# Lab7-8_CH4.net
KiCad netlist of a schematic drawn in Altium Designer
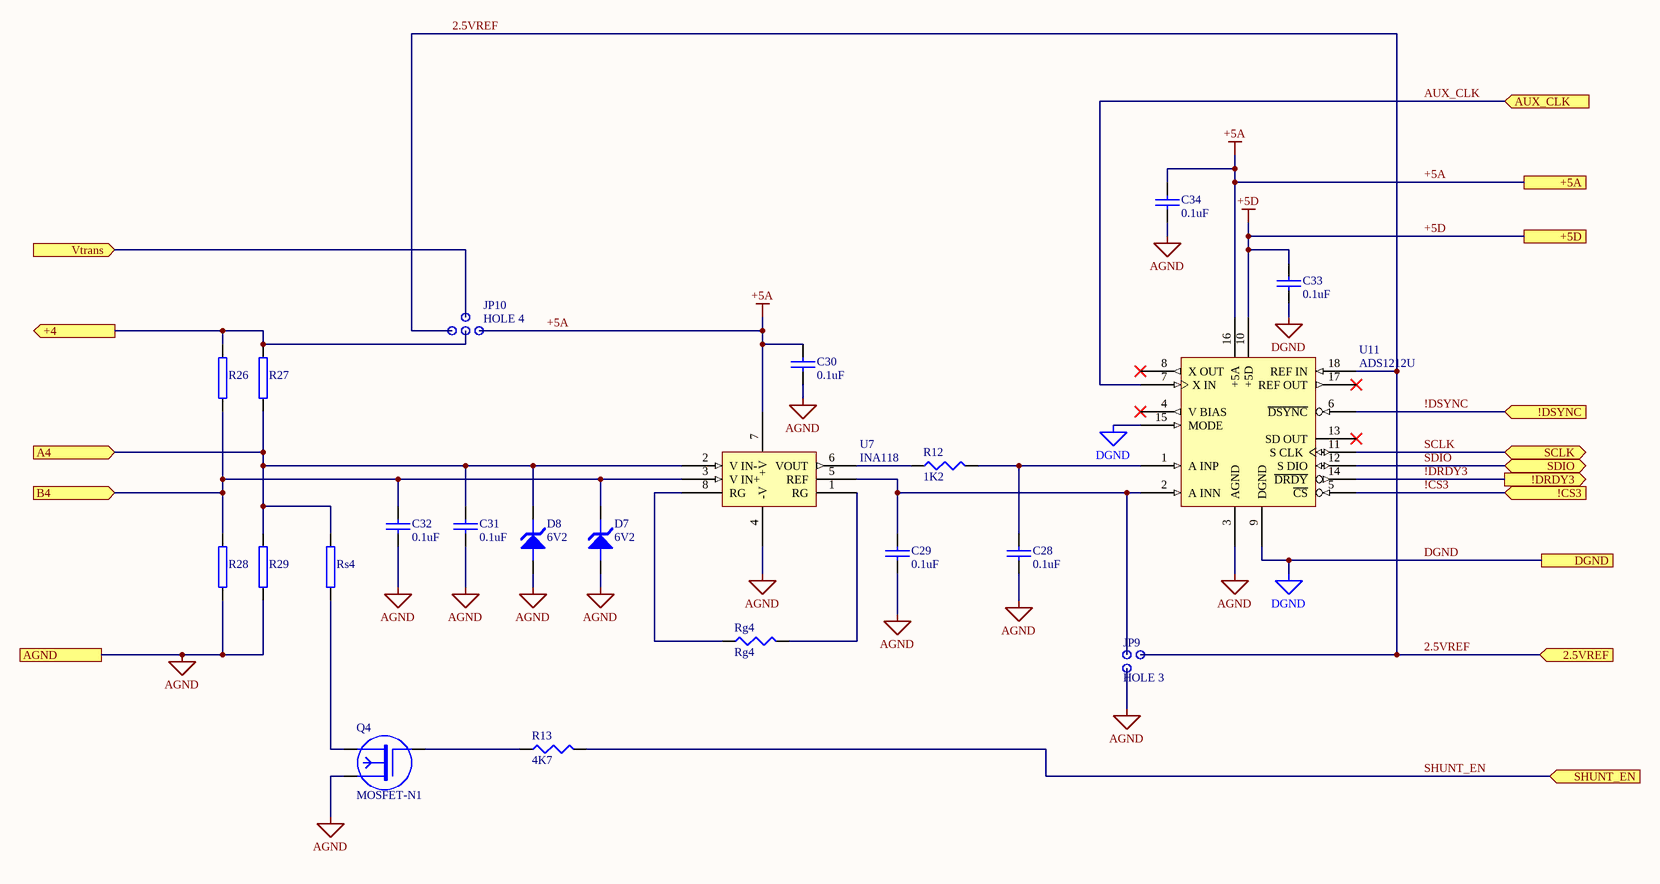
[diagram p0: Lab7-8_CH4.SchDoc]

(export (version "E")
  (design (tool "Eeschema 10.0.6"))
  (components
    (comp (ref "C28")
      (value "0.1uF")
      (footprint "0805")
      (libsource (lib "ECET231_ProjectThree_SCHLIB_Rev02") (part "CAP"))
    )
    (comp (ref "C29")
      (value "0.1uF")
      (footprint "0805")
      (libsource (lib "ECET231_ProjectThree_SCHLIB_Rev02") (part "CAP"))
    )
    (comp (ref "C30")
      (value "0.1uF")
      (footprint "0805")
      (libsource (lib "ECET231_ProjectThree_SCHLIB_Rev02") (part "CAP"))
    )
    (comp (ref "C31")
      (value "0.1uF")
      (footprint "0805")
      (libsource (lib "ECET231_ProjectThree_SCHLIB_Rev02") (part "CAP"))
    )
    (comp (ref "C32")
      (value "0.1uF")
      (footprint "0805")
      (libsource (lib "ECET231_ProjectThree_SCHLIB_Rev02") (part "CAP"))
    )
    (comp (ref "C33")
      (value "0.1uF")
      (footprint "0805")
      (libsource (lib "ECET231_ProjectThree_SCHLIB_Rev02") (part "CAP"))
    )
    (comp (ref "C34")
      (value "0.1uF")
      (footprint "0805")
      (libsource (lib "ECET231_ProjectThree_SCHLIB_Rev02") (part "CAP"))
    )
    (comp (ref "D7")
      (value "6V2")
      (footprint "SOD-123")
      (libsource (lib "ECET231_ProjectThree_SCHLIB_Rev02") (part "ZENER3"))
    )
    (comp (ref "D8")
      (value "6V2")
      (footprint "SOD-123")
      (libsource (lib "ECET231_ProjectThree_SCHLIB_Rev02") (part "ZENER3"))
    )
    (comp (ref "JP9")
      (value "HOLE 3")
      (footprint "RAD0.1A")
      (libsource (lib "ECET231_ProjectThree_SCHLIB_Rev02") (part "HOLE 3"))
    )
    (comp (ref "JP10")
      (value "HOLE 4")
      (footprint "RAD0.1B")
      (libsource (lib "ECET231_ProjectThree_SCHLIB_Rev02") (part "HOLE 4"))
    )
    (comp (ref "Q4")
      (value "MOSFET-N1")
      (footprint "SOT-23")
      (libsource (lib "ECET231_ProjectThree_SCHLIB_Rev02") (part "MOSFET-N1"))
    )
    (comp (ref "R12")
      (value "1K2")
      (footprint "0805")
      (libsource (lib "ECET231_ProjectThree_SCHLIB_Rev02") (part "RES1"))
    )
    (comp (ref "R13")
      (value "4K7")
      (footprint "0805")
      (libsource (lib "ECET231_ProjectThree_SCHLIB_Rev02") (part "RES1"))
    )
    (comp (ref "R26")
      (value "bridge R")
      (footprint "bridge resistor")
      (libsource (lib "ECET231_ProjectThree_SCHLIB_Rev02") (part "RES2"))
    )
    (comp (ref "R27")
      (value "bridge R")
      (footprint "bridge resistor")
      (libsource (lib "ECET231_ProjectThree_SCHLIB_Rev02") (part "RES2"))
    )
    (comp (ref "R28")
      (value "bridge R")
      (footprint "bridge resistor")
      (libsource (lib "ECET231_ProjectThree_SCHLIB_Rev02") (part "RES2"))
    )
    (comp (ref "R29")
      (value "bridge R")
      (footprint "bridge resistor")
      (libsource (lib "ECET231_ProjectThree_SCHLIB_Rev02") (part "RES2"))
    )
    (comp (ref "Rg4")
      (value "Rg4")
      (footprint "0805")
      (libsource (lib "ECET231_ProjectThree_SCHLIB_Rev02") (part "RES1"))
    )
    (comp (ref "Rs4")
      (value "bridge R")
      (footprint "bridge resistor")
      (libsource (lib "ECET231_ProjectThree_SCHLIB_Rev02") (part "RES2"))
    )
    (comp (ref "U7")
      (value "INA118")
      (footprint "SO-8")
      (description "Precision, Low Power Instrumentation Amplifier")
      (libsource (lib "ECET231_ProjectThree_SCHLIB_Rev02") (part "INA118"))
    )
    (comp (ref "U11")
      (value "ADS1212U")
      (footprint "SOIC18")
      (description "22-Bit Analog-to-Digital Converter")
      (libsource (lib "ECET231_ProjectThree_SCHLIB_Rev02") (part "ADS1212U(18)"))
    )
  )
  (nets
    (net (code "1") (name "+5A") (class "Default")
      (node (ref "C30") (pin "1") (pintype "passive"))
      (node (ref "C34") (pin "1") (pintype "passive"))
      (node (ref "JP10") (pin "1") (pinfunction "1_1") (pintype "passive"))
      (node (ref "U11") (pin "16") (pinfunction "+5A_16") (pintype "power_in"))
      (node (ref "U7") (pin "7") (pinfunction "+V_7") (pintype "power_in"))
    )
    (net (code "2") (name "+5D") (class "Default")
      (node (ref "C33") (pin "1") (pintype "passive"))
      (node (ref "U11") (pin "10") (pinfunction "+5D_10") (pintype "power_in"))
    )
    (net (code "3") (name "/!CS3") (class "Default")
      (node (ref "U11") (pin "5") (pinfunction "~{CS}_5") (pintype "input"))
    )
    (net (code "4") (name "/!DRDY3") (class "Default")
      (node (ref "U11") (pin "14") (pinfunction "~{DRDY}_14") (pintype "output"))
    )
    (net (code "5") (name "/!DSYNC") (class "Default")
      (node (ref "U11") (pin "6") (pinfunction "~{DSYNC}_6") (pintype "input"))
    )
    (net (code "6") (name "/+4") (class "Default")
      (node (ref "JP10") (pin "2") (pinfunction "2_2") (pintype "passive"))
      (node (ref "R26") (pin "2") (pintype "passive"))
      (node (ref "R27") (pin "2") (pintype "passive"))
    )
    (net (code "7") (name "/2.5VREF") (class "Default")
      (node (ref "JP10") (pin "4") (pinfunction "4_4") (pintype "passive"))
      (node (ref "JP9") (pin "3") (pinfunction "3_3") (pintype "passive"))
      (node (ref "U11") (pin "18") (pinfunction "REF_IN_18") (pintype "input"))
    )
    (net (code "8") (name "/A4") (class "Default")
      (node (ref "C31") (pin "1") (pintype "passive"))
      (node (ref "D8") (pin "K") (pintype "passive"))
      (node (ref "R27") (pin "1") (pintype "passive"))
      (node (ref "R29") (pin "2") (pintype "passive"))
      (node (ref "Rs4") (pin "2") (pintype "passive"))
      (node (ref "U7") (pin "2") (pinfunction "V_IN-_2") (pintype "input"))
    )
    (net (code "9") (name "/AUX_CLK") (class "Default")
      (node (ref "U11") (pin "7") (pinfunction "X_IN_7") (pintype "input"))
    )
    (net (code "10") (name "/B4") (class "Default")
      (node (ref "C32") (pin "1") (pintype "passive"))
      (node (ref "D7") (pin "K") (pintype "passive"))
      (node (ref "R26") (pin "1") (pintype "passive"))
      (node (ref "R28") (pin "2") (pintype "passive"))
      (node (ref "U7") (pin "3") (pinfunction "V_IN+_3") (pintype "input"))
    )
    (net (code "11") (name "/SCLK") (class "Default")
      (node (ref "U11") (pin "11") (pinfunction "S_CLK_11") (pintype "bidirectional"))
    )
    (net (code "12") (name "/SDIO") (class "Default")
      (node (ref "U11") (pin "12") (pinfunction "S_DIO_12") (pintype "bidirectional"))
    )
    (net (code "13") (name "/SHUNT_EN") (class "Default") (node (ref "R13") (pin "2") (pintype "passive")))
    (net (code "14") (name "/Vtrans") (class "Default")
      (node (ref "JP10") (pin "3") (pinfunction "3_3") (pintype "passive"))
    )
    (net (code "15") (name "AGND") (class "Default")
      (node (ref "C28") (pin "2") (pintype "passive"))
      (node (ref "C29") (pin "2") (pintype "passive"))
      (node (ref "C30") (pin "2") (pintype "passive"))
      (node (ref "C31") (pin "2") (pintype "passive"))
      (node (ref "C32") (pin "2") (pintype "passive"))
      (node (ref "C34") (pin "2") (pintype "passive"))
      (node (ref "D7") (pin "A") (pintype "passive"))
      (node (ref "D8") (pin "A") (pintype "passive"))
      (node (ref "JP9") (pin "1") (pinfunction "1_1") (pintype "passive"))
      (node (ref "Q4") (pin "2") (pintype "passive"))
      (node (ref "R28") (pin "1") (pintype "passive"))
      (node (ref "R29") (pin "1") (pintype "passive"))
      (node (ref "U11") (pin "3") (pinfunction "AGND_3") (pintype "power_in"))
      (node (ref "U7") (pin "4") (pinfunction "-V_4") (pintype "power_in"))
    )
    (net (code "16") (name "DGND") (class "Default")
      (node (ref "C33") (pin "2") (pintype "passive"))
      (node (ref "U11") (pin "15") (pinfunction "MODE_15") (pintype "input"))
      (node (ref "U11") (pin "9") (pinfunction "DGND_9") (pintype "power_in"))
    )
    (net (code "17") (name "Net-(Q4-Pad1)") (class "Default")
      (node (ref "Q4") (pin "1") (pintype "passive"))
      (node (ref "R13") (pin "1") (pintype "passive"))
    )
    (net (code "18") (name "Net-(Q4-Pad3)") (class "Default")
      (node (ref "Q4") (pin "3") (pintype "passive"))
      (node (ref "Rs4") (pin "1") (pintype "passive"))
    )
    (net (code "19") (name "Net-(Rg4-Pad1)") (class "Default")
      (node (ref "Rg4") (pin "1") (pintype "passive"))
      (node (ref "U7") (pin "8") (pinfunction "RG_8") (pintype "passive"))
    )
    (net (code "20") (name "Net-(Rg4-Pad2)") (class "Default")
      (node (ref "Rg4") (pin "2") (pintype "passive"))
      (node (ref "U7") (pin "1") (pinfunction "RG_1") (pintype "passive"))
    )
    (net (code "21") (name "Net-(U7-VOUT)") (class "Default")
      (node (ref "R12") (pin "1") (pintype "passive"))
      (node (ref "U7") (pin "6") (pinfunction "VOUT_6") (pintype "output"))
    )
    (net (code "22") (name "Net-(U11-A_INN)") (class "Default")
      (node (ref "C29") (pin "1") (pintype "passive"))
      (node (ref "JP9") (pin "2") (pinfunction "2_2") (pintype "passive"))
      (node (ref "U11") (pin "2") (pinfunction "A_INN_2") (pintype "input"))
      (node (ref "U7") (pin "5") (pinfunction "REF_5") (pintype "passive"))
    )
    (net (code "23") (name "Net-(U11-A_INP)") (class "Default")
      (node (ref "C28") (pin "1") (pintype "passive"))
      (node (ref "R12") (pin "2") (pintype "passive"))
      (node (ref "U11") (pin "1") (pinfunction "A_INP_1") (pintype "input"))
    )
    (net (code "24") (name "unconnected-(U11-REF_OUT-Pad17)") (class "Default")
      (node (ref "U11") (pin "17") (pinfunction "REF_OUT_17") (pintype "output+no_connect"))
    )
    (net (code "25") (name "unconnected-(U11-SD_OUT-Pad13)") (class "Default")
      (node (ref "U11") (pin "13") (pinfunction "SD_OUT_13") (pintype "tri_state+no_connect"))
    )
    (net (code "26") (name "unconnected-(U11-V_BIAS-Pad4)") (class "Default")
      (node (ref "U11") (pin "4") (pinfunction "V_BIAS_4") (pintype "output+no_connect"))
    )
    (net (code "27") (name "unconnected-(U11-X_OUT-Pad8)") (class "Default")
      (node (ref "U11") (pin "8") (pinfunction "X_OUT_8") (pintype "output+no_connect"))
    )
  )
)
